# cando_pro.net
KiCad netlist of a schematic drawn in Altium Designer
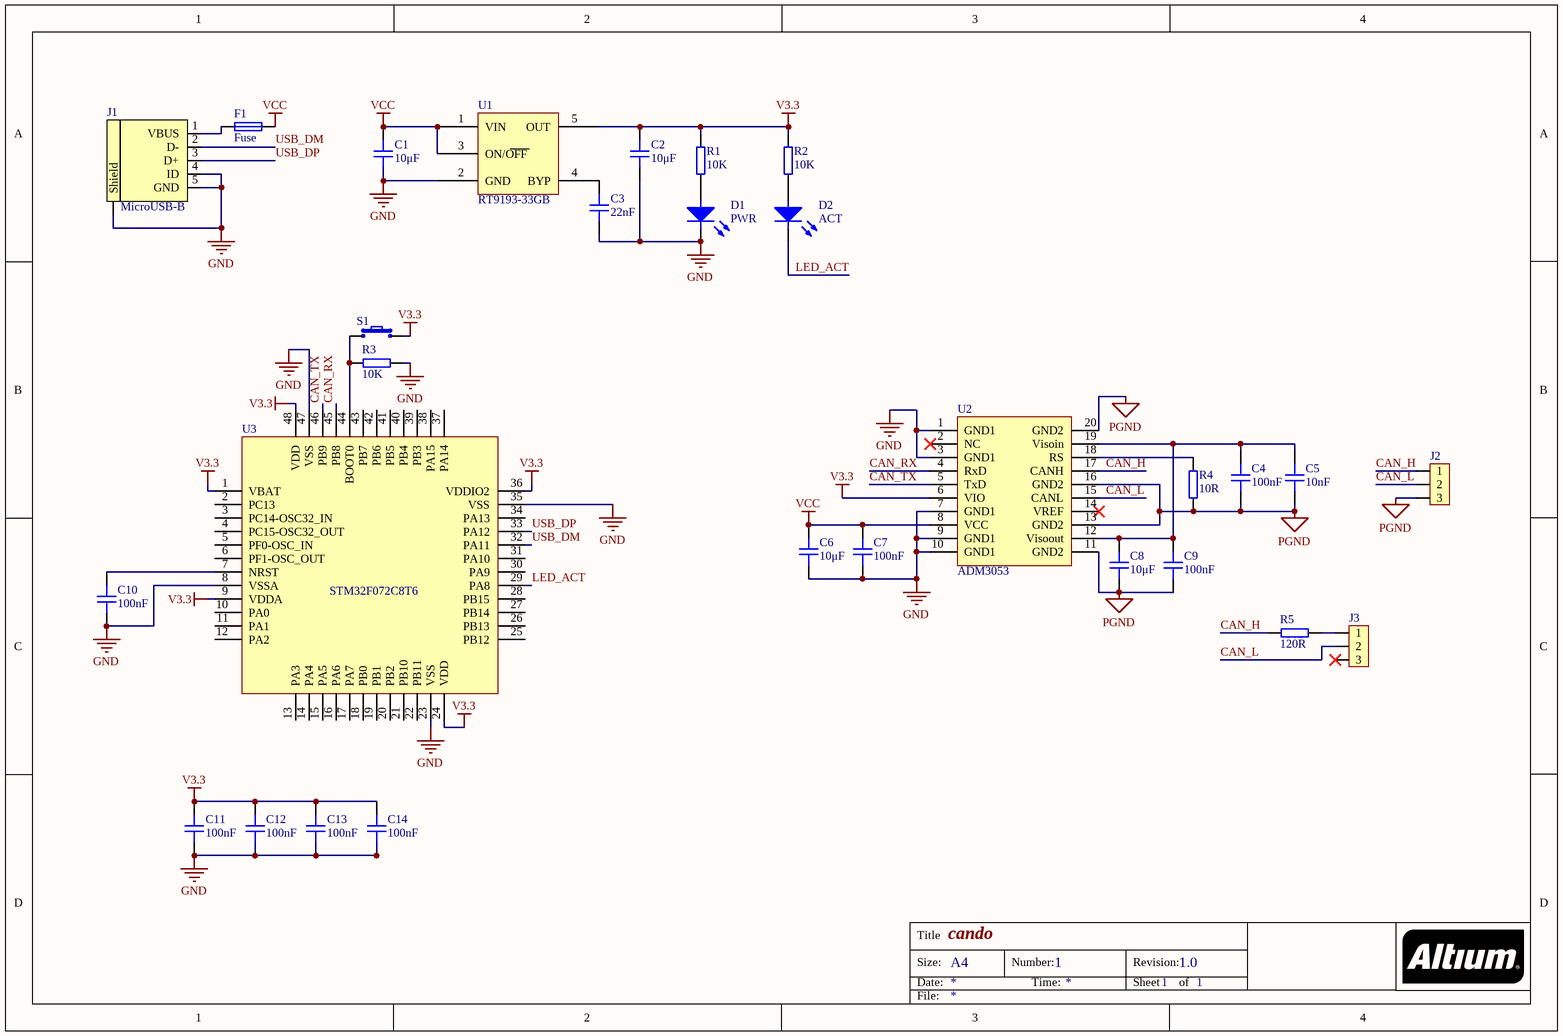
[diagram p0: cando_pro.SchDoc]

(export (version "E")
  (design (tool "Eeschema 10.0.6"))
  (components
    (comp (ref "C1")
      (value "10μF")
      (footprint "0603C")
      (description "Capacitor")
      (libsource (lib "SCH_LIB") (part "CAP"))
    )
    (comp (ref "C2")
      (value "10μF")
      (footprint "0603C")
      (description "Capacitor")
      (libsource (lib "SCH_LIB") (part "CAP"))
    )
    (comp (ref "C3")
      (value "22nF")
      (footprint "0603C")
      (description "Capacitor")
      (libsource (lib "SCH_LIB") (part "CAP"))
    )
    (comp (ref "C4")
      (value "100nF")
      (footprint "0603C")
      (description "Capacitor")
      (libsource (lib "SCH_LIB") (part "CAP"))
    )
    (comp (ref "C5")
      (value "10nF")
      (footprint "0603C")
      (description "Capacitor")
      (libsource (lib "SCH_LIB") (part "CAP"))
    )
    (comp (ref "C6")
      (value "10μF")
      (footprint "0603C")
      (description "Capacitor")
      (libsource (lib "SCH_LIB") (part "CAP"))
    )
    (comp (ref "C7")
      (value "100nF")
      (footprint "0603C")
      (description "Capacitor")
      (libsource (lib "SCH_LIB") (part "CAP"))
    )
    (comp (ref "C8")
      (value "10μF")
      (footprint "0603C")
      (description "Capacitor")
      (libsource (lib "SCH_LIB") (part "CAP"))
    )
    (comp (ref "C9")
      (value "100nF")
      (footprint "0603C")
      (description "Capacitor")
      (libsource (lib "SCH_LIB") (part "CAP"))
    )
    (comp (ref "C10")
      (value "100nF")
      (footprint "0603C")
      (description "Capacitor")
      (libsource (lib "SCH_LIB") (part "CAP"))
    )
    (comp (ref "C11")
      (value "100nF")
      (footprint "0603C")
      (description "Capacitor")
      (libsource (lib "SCH_LIB") (part "CAP"))
    )
    (comp (ref "C12")
      (value "100nF")
      (footprint "0603C")
      (description "Capacitor")
      (libsource (lib "SCH_LIB") (part "CAP"))
    )
    (comp (ref "C13")
      (value "100nF")
      (footprint "0603C")
      (description "Capacitor")
      (libsource (lib "SCH_LIB") (part "CAP"))
    )
    (comp (ref "C14")
      (value "100nF")
      (footprint "0603C")
      (description "Capacitor")
      (libsource (lib "SCH_LIB") (part "CAP"))
    )
    (comp (ref "D1")
      (value "PWR")
      (footprint "LED_0603_GREEN")
      (description "LED")
      (libsource (lib "SCH_LIB") (part "LED"))
    )
    (comp (ref "D2")
      (value "ACT")
      (footprint "LED_0603_BLUE")
      (description "LED")
      (libsource (lib "SCH_LIB") (part "LED"))
    )
    (comp (ref "F1") (value "Fuse") (footprint "0805R") (libsource (lib "SCH_LIB") (part "Fuse")))
    (comp (ref "J1")
      (value "MicroUSB-B")
      (footprint "USB-Micro")
      (description "MicroUSB-B-SMT")
      (libsource (lib "SCH_LIB") (part "MiniUSB-AB-SMT"))
    )
    (comp (ref "J2") (value "~") (footprint "MKDSN-2.54-3P") (libsource (lib "SCH_LIB") (part "Junction_3P")))
    (comp (ref "J3")
      (value "~")
      (footprint "HEADER_2.54_3P")
      (libsource (lib "SCH_LIB") (part "Junction_3P"))
    )
    (comp (ref "R1")
      (value "10K")
      (footprint "0603R")
      (description "Resistor")
      (libsource (lib "SCH_LIB") (part "RES"))
    )
    (comp (ref "R2")
      (value "10K")
      (footprint "0603R")
      (description "Resistor")
      (libsource (lib "SCH_LIB") (part "RES"))
    )
    (comp (ref "R3")
      (value "10K")
      (footprint "0603R")
      (description "Resistor")
      (libsource (lib "SCH_LIB") (part "RES"))
    )
    (comp (ref "R4")
      (value "10R")
      (footprint "0603R")
      (description "Resistor")
      (libsource (lib "SCH_LIB") (part "RES"))
    )
    (comp (ref "R5")
      (value "120R")
      (footprint "0603R")
      (description "Resistor")
      (libsource (lib "SCH_LIB") (part "RES"))
    )
    (comp (ref "S1") (value "Button") (footprint "BTN_3*4") (libsource (lib "SCH_LIB") (part "SW-PB")))
    (comp (ref "U1")
      (value "RT9193-33GB")
      (footprint "SOT-23-5")
      (description "Chip, RT9193-33GB, LDO Regulator")
      (libsource (lib "SCH_LIB") (part "RT9193-33GB"))
    )
    (comp (ref "U2")
      (value "ADM3053")
      (footprint "RW-20")
      (description "IC, Signal and power isolated CAN transceiver")
      (libsource (lib "SCH_LIB") (part "ADM3053"))
    )
    (comp (ref "U3")
      (value "STM32F072C8T6")
      (footprint "STM-LQFP48_N")
      (libsource (lib "SCH_LIB") (part "STM32F072C8T6"))
    )
  )
  (nets
    (net (code "1") (name "/CAN_H") (class "Default")
      (node (ref "J2") (pin "1") (pinfunction "1_1") (pintype "passive"))
      (node (ref "R5") (pin "1") (pinfunction "1_1") (pintype "passive"))
      (node (ref "U2") (pin "17") (pinfunction "CANH_17") (pintype "passive"))
    )
    (net (code "2") (name "/CAN_L") (class "Default")
      (node (ref "J2") (pin "2") (pinfunction "2_2") (pintype "passive"))
      (node (ref "J3") (pin "2") (pinfunction "2_2") (pintype "passive"))
      (node (ref "U2") (pin "15") (pinfunction "CANL_15") (pintype "passive"))
    )
    (net (code "3") (name "/CAN_RX") (class "Default")
      (node (ref "U2") (pin "4") (pinfunction "RxD_4") (pintype "passive"))
      (node (ref "U3") (pin "45") (pinfunction "PB8_45") (pintype "passive"))
    )
    (net (code "4") (name "/CAN_TX") (class "Default")
      (node (ref "U2") (pin "5") (pinfunction "TxD_5") (pintype "passive"))
      (node (ref "U3") (pin "46") (pinfunction "PB9_46") (pintype "passive"))
    )
    (net (code "5") (name "/LED_ACT") (class "Default")
      (node (ref "D2") (pin "2") (pinfunction "K_2") (pintype "passive"))
      (node (ref "U3") (pin "29") (pinfunction "PA8_29") (pintype "passive"))
    )
    (net (code "6") (name "/USB_DM") (class "Default")
      (node (ref "J1") (pin "2") (pinfunction "D-_2") (pintype "passive"))
      (node (ref "U3") (pin "32") (pinfunction "PA11_32") (pintype "passive"))
    )
    (net (code "7") (name "/USB_DP") (class "Default")
      (node (ref "J1") (pin "3") (pinfunction "D+_3") (pintype "passive"))
      (node (ref "U3") (pin "33") (pinfunction "PA12_33") (pintype "passive"))
    )
    (net (code "8") (name "GND") (class "Default")
      (node (ref "C1") (pin "2") (pinfunction "10_2") (pintype "passive"))
      (node (ref "C10") (pin "2") (pinfunction "10_2") (pintype "passive"))
      (node (ref "C11") (pin "2") (pinfunction "10_2") (pintype "passive"))
      (node (ref "C12") (pin "2") (pinfunction "10_2") (pintype "passive"))
      (node (ref "C13") (pin "2") (pinfunction "10_2") (pintype "passive"))
      (node (ref "C14") (pin "2") (pinfunction "10_2") (pintype "passive"))
      (node (ref "C2") (pin "2") (pinfunction "10_2") (pintype "passive"))
      (node (ref "C3") (pin "1") (pinfunction "1_1") (pintype "passive"))
      (node (ref "C6") (pin "2") (pinfunction "10_2") (pintype "passive"))
      (node (ref "C7") (pin "2") (pinfunction "10_2") (pintype "passive"))
      (node (ref "D1") (pin "2") (pinfunction "K_2") (pintype "passive"))
      (node (ref "J1") (pin "4") (pinfunction "ID_4") (pintype "passive"))
      (node (ref "J1") (pin "5") (pinfunction "GND_5") (pintype "power_in"))
      (node (ref "J1") (pin "6") (pinfunction "Shield_6") (pintype "power_in"))
      (node (ref "R3") (pin "2") (pinfunction "2_2") (pintype "passive"))
      (node (ref "U1") (pin "2") (pinfunction "GND_2") (pintype "passive"))
      (node (ref "U2") (pin "1") (pinfunction "GND1_1") (pintype "passive"))
      (node (ref "U2") (pin "10") (pinfunction "GND1_10") (pintype "passive"))
      (node (ref "U2") (pin "3") (pinfunction "GND1_3") (pintype "passive"))
      (node (ref "U2") (pin "7") (pinfunction "GND1_7") (pintype "passive"))
      (node (ref "U2") (pin "9") (pinfunction "GND1_9") (pintype "passive"))
      (node (ref "U3") (pin "23") (pinfunction "VSS_23") (pintype "passive"))
      (node (ref "U3") (pin "35") (pinfunction "VSS_35") (pintype "passive"))
      (node (ref "U3") (pin "47") (pinfunction "VSS_47") (pintype "passive"))
      (node (ref "U3") (pin "8") (pinfunction "VSSA_8") (pintype "passive"))
    )
    (net (code "9") (name "Net-(C3-10)") (class "Default")
      (node (ref "C3") (pin "2") (pinfunction "10_2") (pintype "passive"))
      (node (ref "U1") (pin "4") (pinfunction "BYP_4") (pintype "passive"))
    )
    (net (code "10") (name "Net-(D1-A)") (class "Default")
      (node (ref "D1") (pin "1") (pinfunction "A_1") (pintype "passive"))
      (node (ref "R1") (pin "2") (pinfunction "2_2") (pintype "passive"))
    )
    (net (code "11") (name "Net-(D2-A)") (class "Default")
      (node (ref "D2") (pin "1") (pinfunction "A_1") (pintype "passive"))
      (node (ref "R2") (pin "2") (pinfunction "2_2") (pintype "passive"))
    )
    (net (code "12") (name "Net-(J1-VBUS)") (class "Default")
      (node (ref "F1") (pin "1") (pinfunction "1_1") (pintype "passive"))
      (node (ref "J1") (pin "1") (pinfunction "VBUS_1") (pintype "power_in"))
    )
    (net (code "13") (name "Net-(J3-Pad1)") (class "Default")
      (node (ref "J3") (pin "1") (pinfunction "1_1") (pintype "passive"))
      (node (ref "R5") (pin "2") (pinfunction "2_2") (pintype "passive"))
    )
    (net (code "14") (name "Net-(U2-RS)") (class "Default")
      (node (ref "R4") (pin "2") (pinfunction "2_2") (pintype "passive"))
      (node (ref "U2") (pin "18") (pinfunction "RS_18") (pintype "passive"))
    )
    (net (code "15") (name "Net-(U2-Visoin)") (class "Default")
      (node (ref "C4") (pin "1") (pinfunction "1_1") (pintype "passive"))
      (node (ref "C5") (pin "1") (pinfunction "1_1") (pintype "passive"))
      (node (ref "C8") (pin "1") (pinfunction "1_1") (pintype "passive"))
      (node (ref "C9") (pin "1") (pinfunction "1_1") (pintype "passive"))
      (node (ref "U2") (pin "12") (pinfunction "Visoout_12") (pintype "passive"))
      (node (ref "U2") (pin "19") (pinfunction "Visoin_19") (pintype "passive"))
    )
    (net (code "16") (name "Net-(U3-BOOT0)") (class "Default")
      (node (ref "R3") (pin "1") (pinfunction "1_1") (pintype "passive"))
      (node (ref "S1") (pin "1") (pinfunction "1_1") (pintype "passive"))
      (node (ref "U3") (pin "44") (pinfunction "BOOT0_44") (pintype "passive"))
    )
    (net (code "17") (name "Net-(U3-NRST)") (class "Default")
      (node (ref "C10") (pin "1") (pinfunction "1_1") (pintype "passive"))
      (node (ref "U3") (pin "7") (pinfunction "NRST_7") (pintype "passive"))
    )
    (net (code "18") (name "PGND") (class "Default")
      (node (ref "C4") (pin "2") (pinfunction "10_2") (pintype "passive"))
      (node (ref "C5") (pin "2") (pinfunction "10_2") (pintype "passive"))
      (node (ref "C8") (pin "2") (pinfunction "10_2") (pintype "passive"))
      (node (ref "C9") (pin "2") (pinfunction "10_2") (pintype "passive"))
      (node (ref "J2") (pin "3") (pinfunction "3_3") (pintype "passive"))
      (node (ref "R4") (pin "1") (pinfunction "1_1") (pintype "passive"))
      (node (ref "U2") (pin "11") (pinfunction "GND2_11") (pintype "passive"))
      (node (ref "U2") (pin "13") (pinfunction "GND2_13") (pintype "passive"))
      (node (ref "U2") (pin "16") (pinfunction "GND2_16") (pintype "passive"))
      (node (ref "U2") (pin "20") (pinfunction "GND2_20") (pintype "passive"))
    )
    (net (code "19") (name "V3.3") (class "Default")
      (node (ref "C11") (pin "1") (pinfunction "1_1") (pintype "passive"))
      (node (ref "C12") (pin "1") (pinfunction "1_1") (pintype "passive"))
      (node (ref "C13") (pin "1") (pinfunction "1_1") (pintype "passive"))
      (node (ref "C14") (pin "1") (pinfunction "1_1") (pintype "passive"))
      (node (ref "C2") (pin "1") (pinfunction "1_1") (pintype "passive"))
      (node (ref "R1") (pin "1") (pinfunction "1_1") (pintype "passive"))
      (node (ref "R2") (pin "1") (pinfunction "1_1") (pintype "passive"))
      (node (ref "S1") (pin "2") (pinfunction "2_2") (pintype "passive"))
      (node (ref "U1") (pin "5") (pinfunction "OUT_5") (pintype "passive"))
      (node (ref "U2") (pin "6") (pinfunction "VIO_6") (pintype "passive"))
      (node (ref "U3") (pin "1") (pinfunction "VBAT_1") (pintype "passive"))
      (node (ref "U3") (pin "24") (pinfunction "VDD_24") (pintype "passive"))
      (node (ref "U3") (pin "36") (pinfunction "VDDIO2_36") (pintype "passive"))
      (node (ref "U3") (pin "48") (pinfunction "VDD_48") (pintype "passive"))
      (node (ref "U3") (pin "9") (pinfunction "VDDA_9") (pintype "passive"))
    )
    (net (code "20") (name "VCC") (class "Default")
      (node (ref "C1") (pin "1") (pinfunction "1_1") (pintype "passive"))
      (node (ref "C6") (pin "1") (pinfunction "1_1") (pintype "passive"))
      (node (ref "C7") (pin "1") (pinfunction "1_1") (pintype "passive"))
      (node (ref "F1") (pin "2") (pinfunction "2_2") (pintype "passive"))
      (node (ref "U1") (pin "1") (pinfunction "VIN_1") (pintype "passive"))
      (node (ref "U1") (pin "3") (pinfunction "ON/OFF_3") (pintype "passive"))
      (node (ref "U2") (pin "8") (pinfunction "VCC_8") (pintype "passive"))
    )
    (net (code "21") (name "unconnected-(J3-Pad3)") (class "Default")
      (node (ref "J3") (pin "3") (pinfunction "3_3") (pintype "passive+no_connect"))
    )
    (net (code "22") (name "unconnected-(U2-NC-Pad2)") (class "Default")
      (node (ref "U2") (pin "2") (pinfunction "NC_2") (pintype "passive+no_connect"))
    )
    (net (code "23") (name "unconnected-(U2-VREF-Pad14)") (class "Default")
      (node (ref "U2") (pin "14") (pinfunction "VREF_14") (pintype "passive+no_connect"))
    )
    (net (code "24") (name "unconnected-(U3-PA0-Pad10)") (class "Default")
      (node (ref "U3") (pin "10") (pinfunction "PA0_10") (pintype "passive"))
    )
    (net (code "25") (name "unconnected-(U3-PA1-Pad11)") (class "Default")
      (node (ref "U3") (pin "11") (pinfunction "PA1_11") (pintype "passive"))
    )
    (net (code "26") (name "unconnected-(U3-PA2-Pad12)") (class "Default")
      (node (ref "U3") (pin "12") (pinfunction "PA2_12") (pintype "passive"))
    )
    (net (code "27") (name "unconnected-(U3-PA3-Pad13)") (class "Default")
      (node (ref "U3") (pin "13") (pinfunction "PA3_13") (pintype "passive"))
    )
    (net (code "28") (name "unconnected-(U3-PA4-Pad14)") (class "Default")
      (node (ref "U3") (pin "14") (pinfunction "PA4_14") (pintype "passive"))
    )
    (net (code "29") (name "unconnected-(U3-PA5-Pad15)") (class "Default")
      (node (ref "U3") (pin "15") (pinfunction "PA5_15") (pintype "passive"))
    )
    (net (code "30") (name "unconnected-(U3-PA6-Pad16)") (class "Default")
      (node (ref "U3") (pin "16") (pinfunction "PA6_16") (pintype "passive"))
    )
    (net (code "31") (name "unconnected-(U3-PA7-Pad17)") (class "Default")
      (node (ref "U3") (pin "17") (pinfunction "PA7_17") (pintype "passive"))
    )
    (net (code "32") (name "unconnected-(U3-PA9-Pad30)") (class "Default")
      (node (ref "U3") (pin "30") (pinfunction "PA9_30") (pintype "passive"))
    )
    (net (code "33") (name "unconnected-(U3-PA10-Pad31)") (class "Default")
      (node (ref "U3") (pin "31") (pinfunction "PA10_31") (pintype "passive"))
    )
    (net (code "34") (name "unconnected-(U3-PA13-Pad34)") (class "Default")
      (node (ref "U3") (pin "34") (pinfunction "PA13_34") (pintype "passive"))
    )
    (net (code "35") (name "unconnected-(U3-PA14-Pad37)") (class "Default")
      (node (ref "U3") (pin "37") (pinfunction "PA14_37") (pintype "passive"))
    )
    (net (code "36") (name "unconnected-(U3-PA15-Pad38)") (class "Default")
      (node (ref "U3") (pin "38") (pinfunction "PA15_38") (pintype "passive"))
    )
    (net (code "37") (name "unconnected-(U3-PB0-Pad18)") (class "Default")
      (node (ref "U3") (pin "18") (pinfunction "PB0_18") (pintype "passive"))
    )
    (net (code "38") (name "unconnected-(U3-PB1-Pad19)") (class "Default")
      (node (ref "U3") (pin "19") (pinfunction "PB1_19") (pintype "passive"))
    )
    (net (code "39") (name "unconnected-(U3-PB2-Pad20)") (class "Default")
      (node (ref "U3") (pin "20") (pinfunction "PB2_20") (pintype "passive"))
    )
    (net (code "40") (name "unconnected-(U3-PB3-Pad39)") (class "Default")
      (node (ref "U3") (pin "39") (pinfunction "PB3_39") (pintype "passive"))
    )
    (net (code "41") (name "unconnected-(U3-PB4-Pad40)") (class "Default")
      (node (ref "U3") (pin "40") (pinfunction "PB4_40") (pintype "passive"))
    )
    (net (code "42") (name "unconnected-(U3-PB5-Pad41)") (class "Default")
      (node (ref "U3") (pin "41") (pinfunction "PB5_41") (pintype "passive"))
    )
    (net (code "43") (name "unconnected-(U3-PB6-Pad42)") (class "Default")
      (node (ref "U3") (pin "42") (pinfunction "PB6_42") (pintype "passive"))
    )
    (net (code "44") (name "unconnected-(U3-PB7-Pad43)") (class "Default")
      (node (ref "U3") (pin "43") (pinfunction "PB7_43") (pintype "passive"))
    )
    (net (code "45") (name "unconnected-(U3-PB10-Pad21)") (class "Default")
      (node (ref "U3") (pin "21") (pinfunction "PB10_21") (pintype "passive"))
    )
    (net (code "46") (name "unconnected-(U3-PB11-Pad22)") (class "Default")
      (node (ref "U3") (pin "22") (pinfunction "PB11_22") (pintype "passive"))
    )
    (net (code "47") (name "unconnected-(U3-PB12-Pad25)") (class "Default")
      (node (ref "U3") (pin "25") (pinfunction "PB12_25") (pintype "passive"))
    )
    (net (code "48") (name "unconnected-(U3-PB13-Pad26)") (class "Default")
      (node (ref "U3") (pin "26") (pinfunction "PB13_26") (pintype "passive"))
    )
    (net (code "49") (name "unconnected-(U3-PB14-Pad27)") (class "Default")
      (node (ref "U3") (pin "27") (pinfunction "PB14_27") (pintype "passive"))
    )
    (net (code "50") (name "unconnected-(U3-PB15-Pad28)") (class "Default")
      (node (ref "U3") (pin "28") (pinfunction "PB15_28") (pintype "passive"))
    )
    (net (code "51") (name "unconnected-(U3-PC13-Pad2)") (class "Default")
      (node (ref "U3") (pin "2") (pinfunction "PC13_2") (pintype "passive"))
    )
    (net (code "52") (name "unconnected-(U3-PC14-OSC32_IN-Pad3)") (class "Default")
      (node (ref "U3") (pin "3") (pinfunction "PC14-OSC32_IN_3") (pintype "passive"))
    )
    (net (code "53") (name "unconnected-(U3-PC15-OSC32_OUT-Pad4)") (class "Default")
      (node (ref "U3") (pin "4") (pinfunction "PC15-OSC32_OUT_4") (pintype "passive"))
    )
    (net (code "54") (name "unconnected-(U3-PF0-OSC_IN-Pad5)") (class "Default")
      (node (ref "U3") (pin "5") (pinfunction "PF0-OSC_IN_5") (pintype "passive"))
    )
    (net (code "55") (name "unconnected-(U3-PF1-OSC_OUT-Pad6)") (class "Default")
      (node (ref "U3") (pin "6") (pinfunction "PF1-OSC_OUT_6") (pintype "passive"))
    )
  )
)
